# ESP8266-breakout.net
KiCad netlist of a schematic drawn in EAGLE
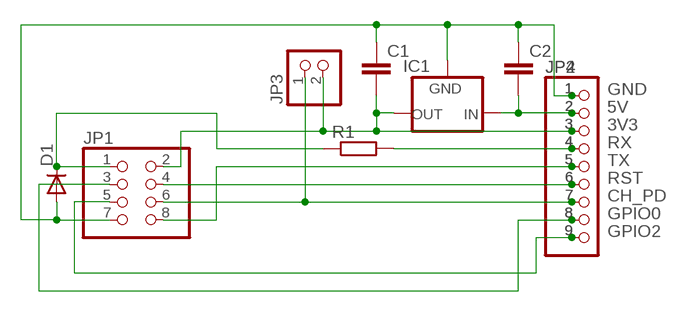
[diagram p0: schematic, sheet 1]

(export (version "E")
  (design (tool "Eeschema 10.0.6"))
  (components
    (comp (ref "C1")
      (value "C-EU025-025X050")
      (footprint "eagle-import:C025-025X050")
      (libsource (lib "eagle-import") (part "C-EU025-025X050"))
    )
    (comp (ref "C2")
      (value "C-EU025-025X050")
      (footprint "eagle-import:C025-025X050")
      (libsource (lib "eagle-import") (part "C-EU025-025X050"))
    )
    (comp (ref "D1")
      (value "DIODE-D-5")
      (footprint "eagle-import:D-5")
      (libsource (lib "eagle-import") (part "DIODE-D-5"))
    )
    (comp (ref "IC1")
      (value "V_REG_78XX-TO-220")
      (footprint "eagle-import:TO-220-ALT")
      (libsource (lib "eagle-import") (part "V_REG_78XX-TO-220"))
    )
    (comp (ref "JP1")
      (value "PINHD-2X4")
      (footprint "eagle-import:2X04")
      (libsource (lib "eagle-import") (part "PINHD-2X4"))
    )
    (comp (ref "JP2")
      (value "PINHD-1X9")
      (footprint "eagle-import:1X09")
      (libsource (lib "eagle-import") (part "PINHD-1X9"))
    )
    (comp (ref "JP3")
      (value "PINHD-1X2")
      (footprint "eagle-import:1X02")
      (libsource (lib "eagle-import") (part "PINHD-1X2"))
    )
    (comp (ref "JP4")
      (value "PINHD-1X9")
      (footprint "eagle-import:1X09")
      (libsource (lib "eagle-import") (part "PINHD-1X9"))
    )
    (comp (ref "R1")
      (value "R-EU_0204/7")
      (footprint "eagle-import:0204_7")
      (libsource (lib "eagle-import") (part "R-EU_0204/7"))
    )
  )
  (nets
    (net (code "1") (name "/3V3") (class "Default")
      (node (ref "C1") (pin "2") (pinfunction "2_2") (pintype "passive"))
      (node (ref "IC1") (pin "OUT") (pinfunction "OUT_OUT") (pintype "output"))
      (node (ref "JP1") (pin "2") (pinfunction "2_2") (pintype "passive"))
      (node (ref "JP2") (pin "3") (pinfunction "3_3") (pintype "passive"))
      (node (ref "JP3") (pin "2") (pinfunction "2_2") (pintype "passive"))
      (node (ref "JP4") (pin "3") (pinfunction "3_3") (pintype "passive"))
    )
    (net (code "2") (name "/5V") (class "Default")
      (node (ref "C2") (pin "2") (pinfunction "2_2") (pintype "passive"))
      (node (ref "IC1") (pin "IN") (pinfunction "IN_IN") (pintype "input"))
      (node (ref "JP2") (pin "2") (pinfunction "2_2") (pintype "passive"))
      (node (ref "JP4") (pin "2") (pinfunction "2_2") (pintype "passive"))
    )
    (net (code "3") (name "/CH_PD") (class "Default")
      (node (ref "JP1") (pin "6") (pinfunction "6_6") (pintype "passive"))
      (node (ref "JP2") (pin "7") (pinfunction "7_7") (pintype "passive"))
      (node (ref "JP3") (pin "1") (pinfunction "1_1") (pintype "passive"))
      (node (ref "JP4") (pin "7") (pinfunction "7_7") (pintype "passive"))
    )
    (net (code "4") (name "/GND") (class "Default")
      (node (ref "C1") (pin "1") (pinfunction "1_1") (pintype "passive"))
      (node (ref "C2") (pin "1") (pinfunction "1_1") (pintype "passive"))
      (node (ref "D1") (pin "A") (pinfunction "A_A") (pintype "passive"))
      (node (ref "IC1") (pin "GND") (pinfunction "GND_GND") (pintype "input"))
      (node (ref "JP1") (pin "7") (pinfunction "7_7") (pintype "passive"))
      (node (ref "JP2") (pin "1") (pinfunction "1_1") (pintype "passive"))
      (node (ref "JP4") (pin "1") (pinfunction "1_1") (pintype "passive"))
    )
    (net (code "5") (name "/GPIO0") (class "Default")
      (node (ref "JP1") (pin "3") (pinfunction "3_3") (pintype "passive"))
      (node (ref "JP2") (pin "8") (pinfunction "8_8") (pintype "passive"))
      (node (ref "JP4") (pin "8") (pinfunction "8_8") (pintype "passive"))
    )
    (net (code "6") (name "/GPIO2") (class "Default")
      (node (ref "JP1") (pin "5") (pinfunction "5_5") (pintype "passive"))
      (node (ref "JP2") (pin "9") (pinfunction "9_9") (pintype "passive"))
      (node (ref "JP4") (pin "9") (pinfunction "9_9") (pintype "passive"))
    )
    (net (code "7") (name "/RST") (class "Default")
      (node (ref "JP1") (pin "4") (pinfunction "4_4") (pintype "passive"))
      (node (ref "JP2") (pin "6") (pinfunction "6_6") (pintype "passive"))
      (node (ref "JP4") (pin "6") (pinfunction "6_6") (pintype "passive"))
    )
    (net (code "8") (name "/RX") (class "Default")
      (node (ref "JP2") (pin "4") (pinfunction "4_4") (pintype "passive"))
      (node (ref "JP4") (pin "4") (pinfunction "4_4") (pintype "passive"))
      (node (ref "R1") (pin "2") (pinfunction "2_2") (pintype "passive"))
    )
    (net (code "9") (name "/TX") (class "Default")
      (node (ref "JP1") (pin "8") (pinfunction "8_8") (pintype "passive"))
      (node (ref "JP2") (pin "5") (pinfunction "5_5") (pintype "passive"))
      (node (ref "JP4") (pin "5") (pinfunction "5_5") (pintype "passive"))
    )
    (net (code "10") (name "Net-(D1-PadC)") (class "Default")
      (node (ref "D1") (pin "C") (pinfunction "C_C") (pintype "passive"))
      (node (ref "JP1") (pin "1") (pinfunction "1_1") (pintype "passive"))
      (node (ref "R1") (pin "1") (pinfunction "1_1") (pintype "passive"))
    )
  )
)
